# badge3.net
KiCad netlist of a schematic drawn in Altium Designer
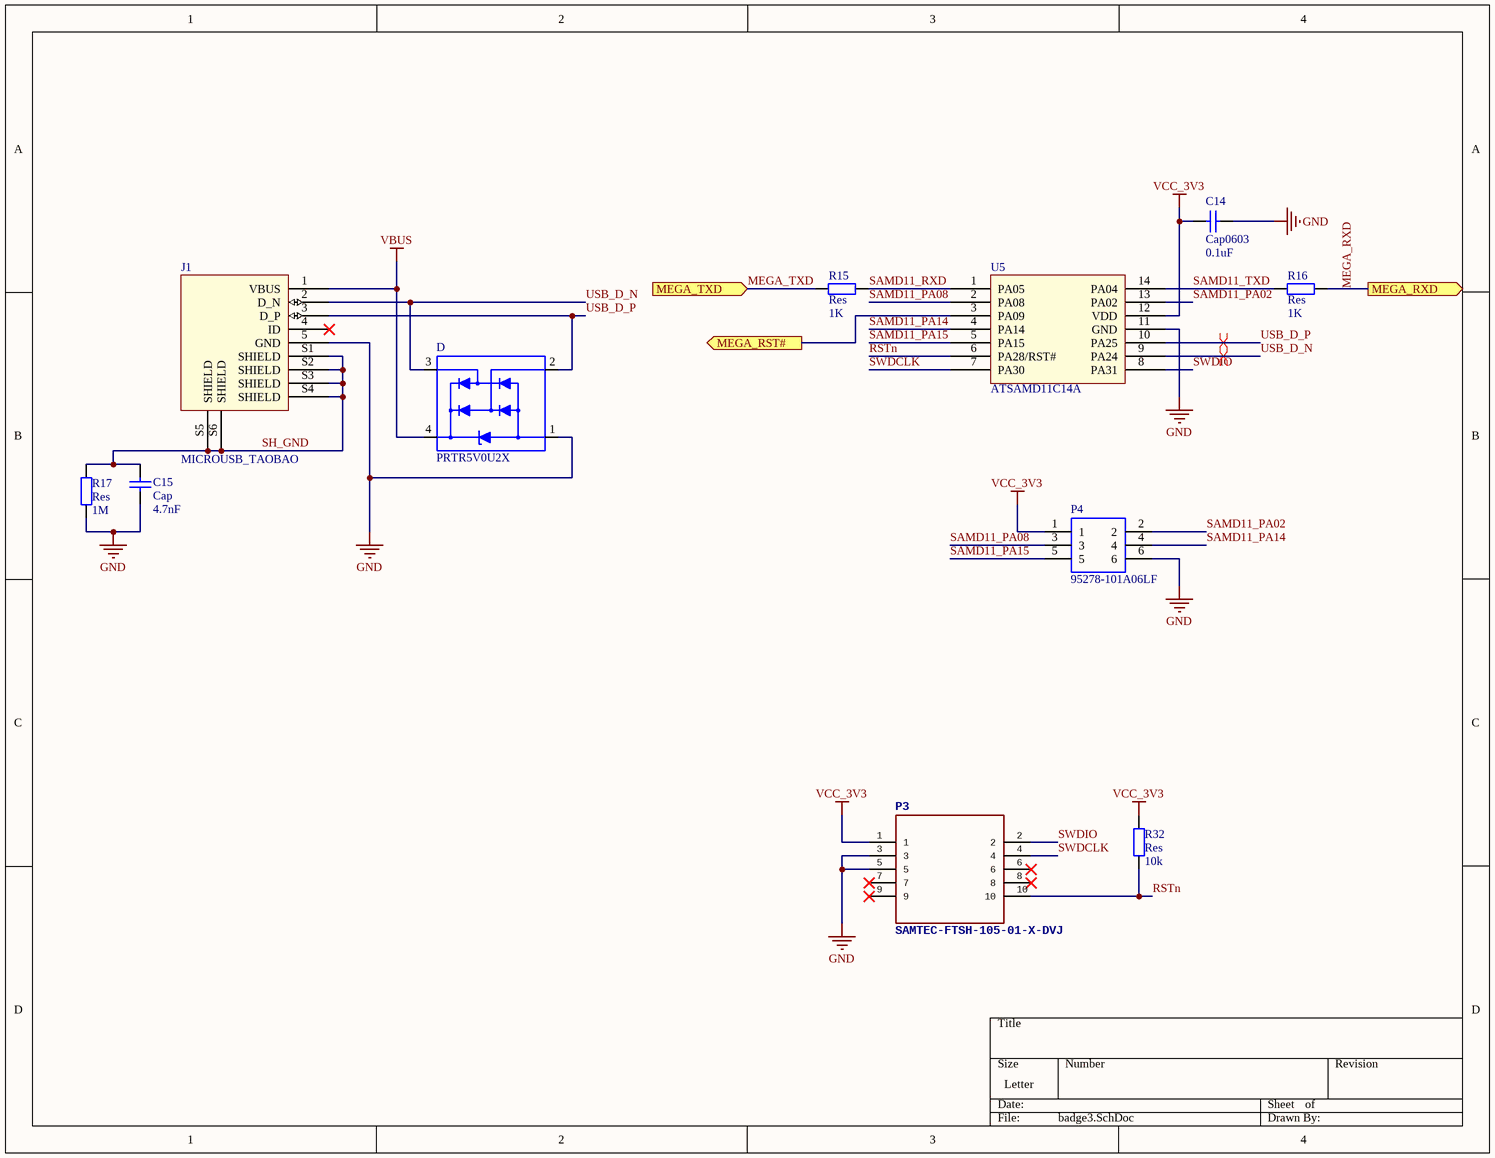
[diagram p0: badge3.SchDoc]

(export (version "E")
  (design (tool "Eeschema 10.0.6"))
  (components
    (comp (ref "C14")
      (value "Cap0603")
      (footprint "C0603")
      (description "Capacitor")
      (fields
        (field (name "ALTIUM_VALUE") "0.1uF")
        (field (name "MF") "KEMET")
        (field (name "MP") "C0603C104Z3VACTU")
        (field (name "PUBLISHER") "Altium Limited")
      )
      (libsource (lib "badge") (part "Cap0603"))
    )
    (comp (ref "C15")
      (value "Cap")
      (footprint "C0805")
      (description "Capacitor")
      (fields
        (field (name "ALTIUM_VALUE") "4.7nF")
        (field (name "MP") "C0805C472KDRACTU")
        (field (name "MF") "KEMET")
        (field (name "PUBLISHER") "Altium Limited")
      )
      (libsource (lib "badge") (part "Cap"))
    )
    (comp (ref "D")
      (value "PRTR5V0U2X")
      (footprint "SOT190P230X110-4N")
      (description "Clamp Ipp Tvs Diode Surface Mount SOT-143B")
      (fields (field (name "MF") "NXP Semiconductors"))
      (libsource (lib "badge") (part "PRTR5V0U2X"))
    )
    (comp (ref "J1")
      (value "MICROUSB_TAOBAO")
      (footprint "MICROUSB_TAOBAO")
      (fields (field (name "MF") "DNP"))
      (libsource (lib "badge") (part "MICROUSB_TAOBAO"))
    )
    (comp (ref "P3")
      (value "SAMTEC-FTSH-105-01-X-DVJ")
      (footprint "SAMTEC-FTSH-105-01-X-DV")
      (fields (field (name "MF") "Samtec") (field (name "MP") "FTS-105-01-L-DV"))
      (libsource (lib "badge") (part "SAMTEC-FTSH-105-01-X-DVJ"))
    )
    (comp (ref "P4")
      (value "95278-101A06LF")
      (footprint "AMPHENOL_95278-101A06LF")
      (description "Connector Header Surface Mount 6 position 0.100 _2.54mm_")
      (fields (field (name "MF") "Amphenol ICC"))
      (libsource (lib "badge") (part "95278-101A06LF"))
    )
    (comp (ref "R15")
      (value "Res")
      (footprint "R0603")
      (description "Resistor")
      (fields
        (field (name "ALTIUM_VALUE") "1K")
        (field (name "MF") "Yageo")
        (field (name "MP") "RC0603JR-071KL")
        (field (name "PUBLISHER") "Altium Limited")
      )
      (libsource (lib "badge") (part "Res"))
    )
    (comp (ref "R16")
      (value "Res")
      (footprint "R0603")
      (description "Resistor")
      (fields
        (field (name "ALTIUM_VALUE") "1K")
        (field (name "MF") "Yageo")
        (field (name "MP") "RC0603JR-071KL")
        (field (name "PUBLISHER") "Altium Limited")
      )
      (libsource (lib "badge") (part "Res"))
    )
    (comp (ref "R17")
      (value "Res")
      (footprint "R0603")
      (description "Resistor")
      (fields
        (field (name "ALTIUM_VALUE") "1M")
        (field (name "MF") "Yageo")
        (field (name "MP") "RC0603FR-071ML")
        (field (name "PUBLISHER") "Altium Limited")
      )
      (libsource (lib "") (part "Res_1"))
    )
    (comp (ref "R32")
      (value "Res")
      (footprint "R0603")
      (description "Resistor")
      (fields
        (field (name "ALTIUM_VALUE") "10k")
        (field (name "MF") "Yageo")
        (field (name "MP") "RC0603JR-0710KL")
        (field (name "PUBLISHER") "Altium Limited")
      )
      (libsource (lib "") (part "Res_1"))
    )
    (comp (ref "U5")
      (value "ATSAMD11C14A")
      (footprint "SOIC127P600X175-14N")
      (fields (field (name "MF") "Atmel") (field (name "MP") "ATSAMD11C14A-SSNTDKR-ND"))
      (libsource (lib "badge") (part "ATSAMD11C14A"))
    )
  )
  (nets
    (net (code "1") (name "/MEGA_RST#") (class "Default")
      (node (ref "U5") (pin "3") (pinfunction "PA09_3") (pintype "passive"))
    )
    (net (code "2") (name "/MEGA_RXD") (class "Default")
      (node (ref "R16") (pin "2") (pinfunction "2_2") (pintype "passive"))
    )
    (net (code "3") (name "/MEGA_TXD") (class "Default")
      (node (ref "R15") (pin "1") (pinfunction "1_1") (pintype "passive"))
    )
    (net (code "4") (name "/RSTn") (class "Default")
      (node (ref "P3") (pin "10") (pinfunction "10_10") (pintype "passive"))
      (node (ref "R32") (pin "1") (pinfunction "1_1") (pintype "passive"))
      (node (ref "U5") (pin "6") (pinfunction "PA28/RST#_6") (pintype "passive"))
    )
    (net (code "5") (name "/SAMD11_PA02") (class "Default")
      (node (ref "P4") (pin "2") (pinfunction "2_2") (pintype "passive"))
      (node (ref "U5") (pin "13") (pinfunction "PA02_13") (pintype "passive"))
    )
    (net (code "6") (name "/SAMD11_PA08") (class "Default")
      (node (ref "P4") (pin "3") (pinfunction "3_3") (pintype "passive"))
      (node (ref "U5") (pin "2") (pinfunction "PA08_2") (pintype "passive"))
    )
    (net (code "7") (name "/SAMD11_PA14") (class "Default")
      (node (ref "P4") (pin "4") (pinfunction "4_4") (pintype "passive"))
      (node (ref "U5") (pin "4") (pinfunction "PA14_4") (pintype "passive"))
    )
    (net (code "8") (name "/SAMD11_PA15") (class "Default")
      (node (ref "P4") (pin "5") (pinfunction "5_5") (pintype "passive"))
      (node (ref "U5") (pin "5") (pinfunction "PA15_5") (pintype "passive"))
    )
    (net (code "9") (name "/SAMD11_RXD") (class "Default")
      (node (ref "R15") (pin "2") (pinfunction "2_2") (pintype "passive"))
      (node (ref "U5") (pin "1") (pinfunction "PA05_1") (pintype "passive"))
    )
    (net (code "10") (name "/SAMD11_TXD") (class "Default")
      (node (ref "R16") (pin "1") (pinfunction "1_1") (pintype "passive"))
      (node (ref "U5") (pin "14") (pinfunction "PA04_14") (pintype "passive"))
    )
    (net (code "11") (name "/SH_GND") (class "Default")
      (node (ref "C15") (pin "2") (pinfunction "2_2") (pintype "passive"))
      (node (ref "J1") (pin "S1") (pinfunction "SHIELD_S1") (pintype "passive"))
      (node (ref "J1") (pin "S2") (pinfunction "SHIELD_S2") (pintype "passive"))
      (node (ref "J1") (pin "S3") (pinfunction "SHIELD_S3") (pintype "passive"))
      (node (ref "J1") (pin "S4") (pinfunction "SHIELD_S4") (pintype "passive"))
      (node (ref "J1") (pin "S5") (pinfunction "SHIELD_S5") (pintype "passive"))
      (node (ref "J1") (pin "S6") (pinfunction "SHIELD_S6") (pintype "passive"))
      (node (ref "R17") (pin "2") (pinfunction "2_2") (pintype "passive"))
    )
    (net (code "12") (name "/SWDCLK") (class "Default")
      (node (ref "P3") (pin "4") (pinfunction "4_4") (pintype "passive"))
      (node (ref "U5") (pin "7") (pinfunction "PA30_7") (pintype "passive"))
    )
    (net (code "13") (name "/SWDIO") (class "Default")
      (node (ref "P3") (pin "2") (pinfunction "2_2") (pintype "passive"))
      (node (ref "U5") (pin "8") (pinfunction "PA31_8") (pintype "passive"))
    )
    (net (code "14") (name "/USB_D_N") (class "Default")
      (node (ref "D") (pin "3") (pinfunction "I/O_2_3") (pintype "passive"))
      (node (ref "J1") (pin "2") (pinfunction "D_N_2") (pintype "bidirectional"))
      (node (ref "U5") (pin "9") (pinfunction "PA24_9") (pintype "passive"))
    )
    (net (code "15") (name "/USB_D_P") (class "Default")
      (node (ref "D") (pin "2") (pinfunction "I/O_1_2") (pintype "passive"))
      (node (ref "J1") (pin "3") (pinfunction "D_P_3") (pintype "bidirectional"))
      (node (ref "U5") (pin "10") (pinfunction "PA25_10") (pintype "passive"))
    )
    (net (code "16") (name "GND") (class "Default")
      (node (ref "C14") (pin "2") (pinfunction "2_2") (pintype "passive"))
      (node (ref "C15") (pin "1") (pinfunction "1_1") (pintype "passive"))
      (node (ref "D") (pin "1") (pinfunction "GND_1") (pintype "passive"))
      (node (ref "J1") (pin "5") (pinfunction "GND_5") (pintype "power_in"))
      (node (ref "P3") (pin "3") (pinfunction "3_3") (pintype "passive"))
      (node (ref "P3") (pin "5") (pinfunction "5_5") (pintype "passive"))
      (node (ref "P4") (pin "6") (pinfunction "6_6") (pintype "passive"))
      (node (ref "R17") (pin "1") (pinfunction "1_1") (pintype "passive"))
      (node (ref "U5") (pin "11") (pinfunction "GND_11") (pintype "passive"))
    )
    (net (code "17") (name "VBUS") (class "Default")
      (node (ref "D") (pin "4") (pinfunction "VCC_4") (pintype "passive"))
      (node (ref "J1") (pin "1") (pinfunction "VBUS_1") (pintype "power_in"))
    )
    (net (code "18") (name "VCC_3V3") (class "Default")
      (node (ref "C14") (pin "1") (pinfunction "1_1") (pintype "passive"))
      (node (ref "P3") (pin "1") (pinfunction "1_1") (pintype "passive"))
      (node (ref "P4") (pin "1") (pinfunction "1_1") (pintype "passive"))
      (node (ref "R32") (pin "2") (pinfunction "2_2") (pintype "passive"))
      (node (ref "U5") (pin "12") (pinfunction "VDD_12") (pintype "passive"))
    )
    (net (code "19") (name "unconnected-(J1-ID-Pad4)") (class "Default")
      (node (ref "J1") (pin "4") (pinfunction "ID_4") (pintype "passive+no_connect"))
    )
    (net (code "20") (name "unconnected-(P3-Pad6)") (class "Default")
      (node (ref "P3") (pin "6") (pinfunction "6_6") (pintype "passive+no_connect"))
    )
    (net (code "21") (name "unconnected-(P3-Pad7)") (class "Default")
      (node (ref "P3") (pin "7") (pinfunction "7_7") (pintype "passive+no_connect"))
    )
    (net (code "22") (name "unconnected-(P3-Pad8)") (class "Default")
      (node (ref "P3") (pin "8") (pinfunction "8_8") (pintype "passive+no_connect"))
    )
    (net (code "23") (name "unconnected-(P3-Pad9)") (class "Default")
      (node (ref "P3") (pin "9") (pinfunction "9_9") (pintype "passive+no_connect"))
    )
  )
)
